# ATmega328P.net
KiCad netlist of a schematic drawn in Altium Designer
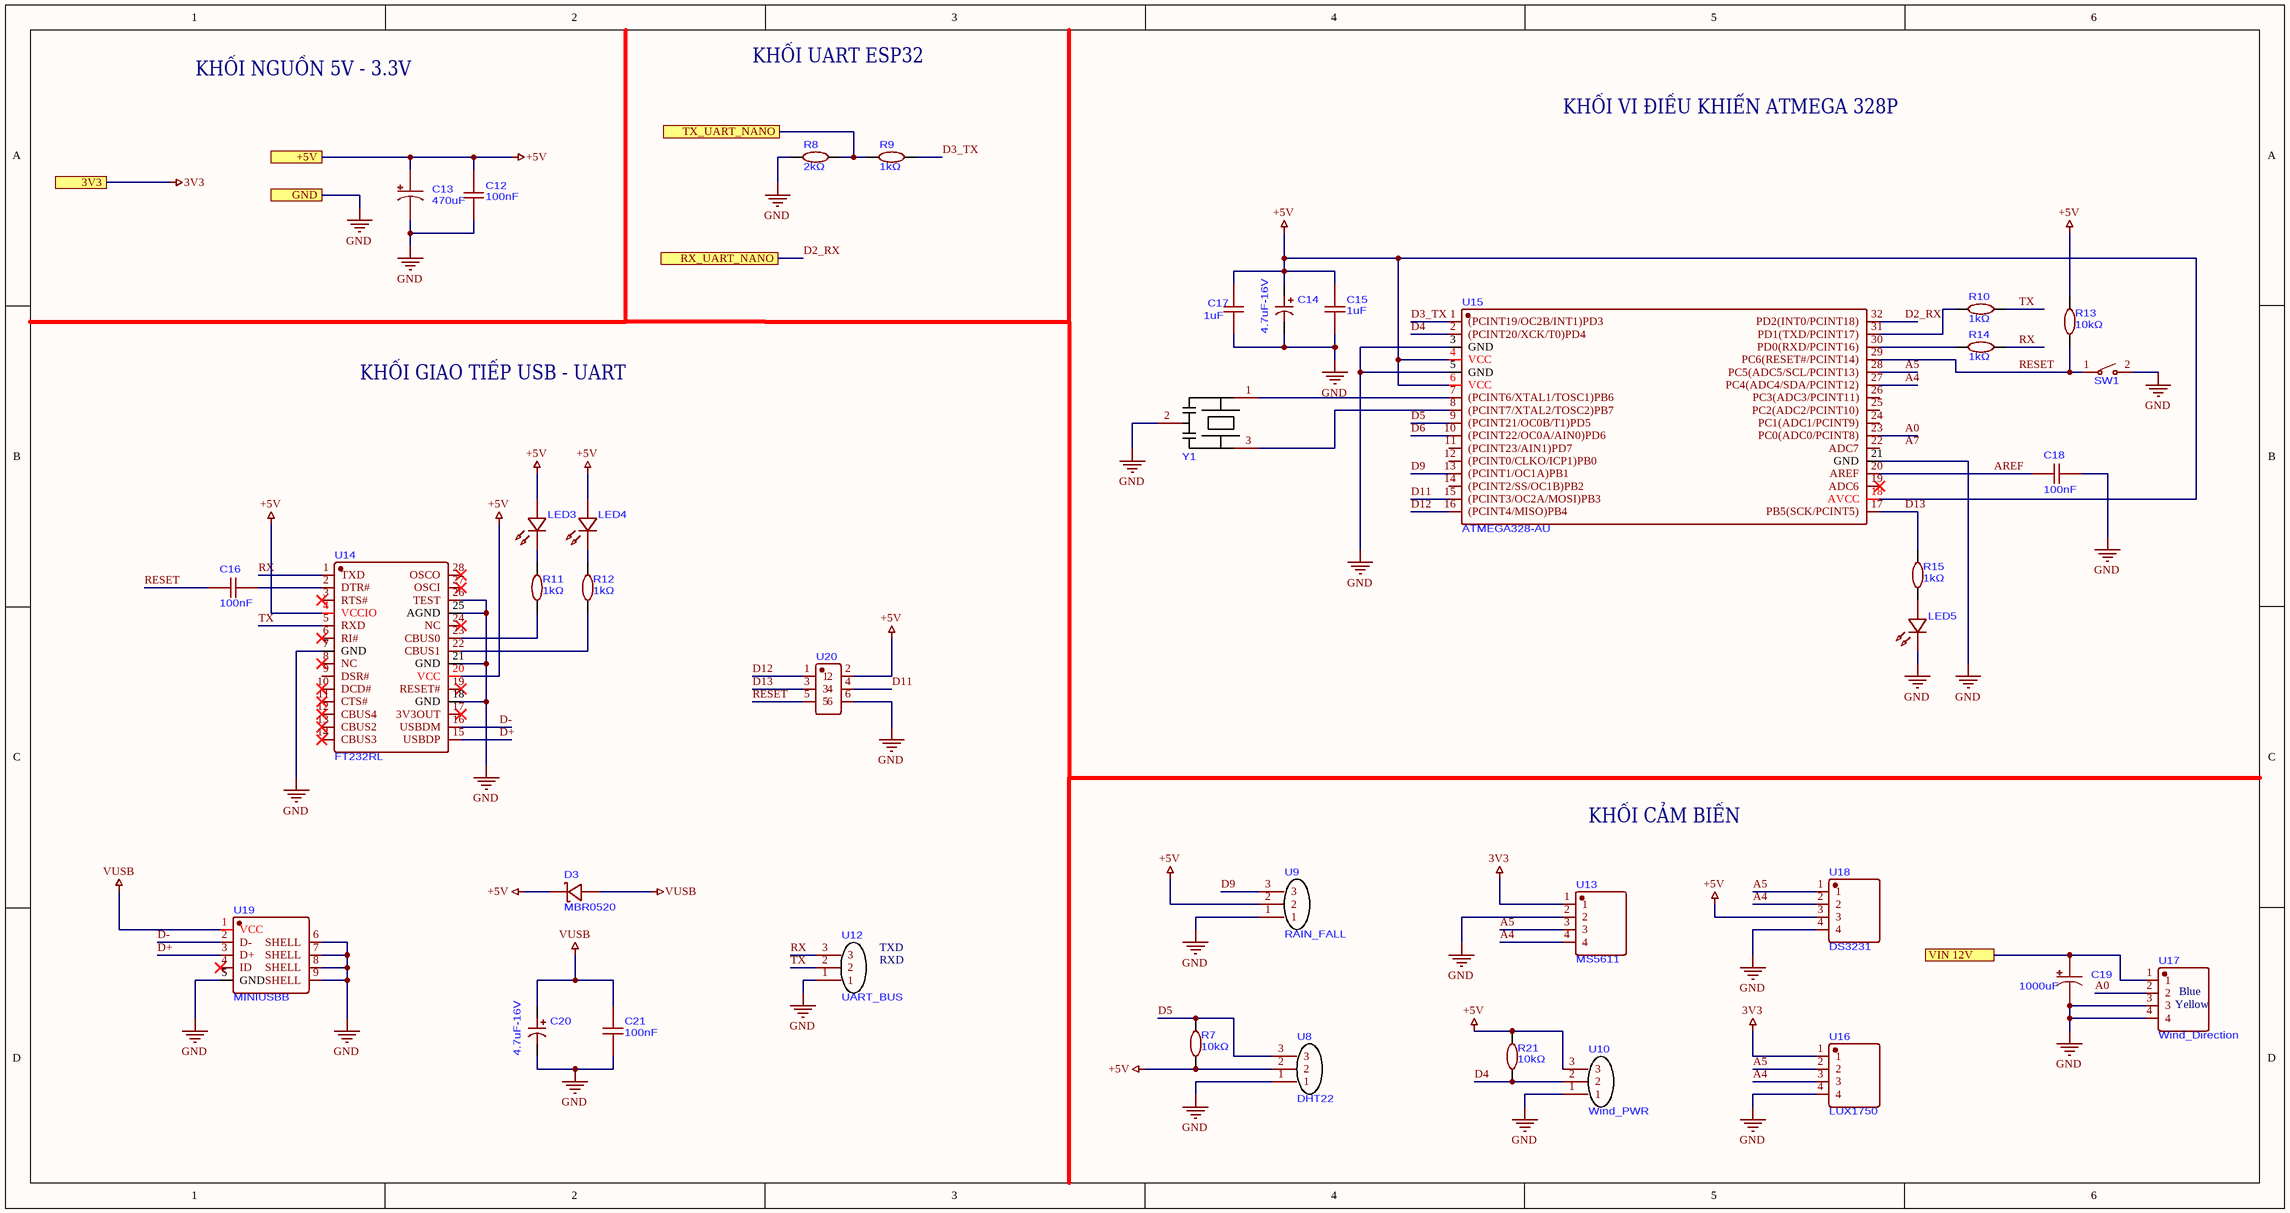
[diagram p0: ATmega328P.SchDoc]

(export (version "E")
  (design (tool "Eeschema 10.0.6"))
  (components
    (comp (ref "C12")
      (value "100nF")
      (footprint "C0805")
      (libsource (lib "CAP 0.1uF") (part "CC0805KRX7R9BB104"))
    )
    (comp (ref "C13")
      (value "470uF")
      (footprint "CAP-SMD_BD10.0-L10.3-W10.3-LS11.0-R-RD")
      (libsource (lib "CAP +") (part "VEJ102M1ATR-1010"))
    )
    (comp (ref "C14")
      (value "4.7uF-16V")
      (footprint "CAP-SMD_L6.0-W3.2-FD")
      (libsource (lib "CAP + 4.7 uF") (part "TCJC475M063R0200"))
    )
    (comp (ref "C15")
      (value "1uF")
      (footprint "C0805")
      (libsource (lib "cap 1uF_0805") (part "TCC0805X7R105K250DTS"))
    )
    (comp (ref "C16")
      (value "100nF")
      (footprint "C0805")
      (libsource (lib "CAP 0.1uF") (part "CC0805KRX7R9BB104"))
    )
    (comp (ref "C17")
      (value "1uF")
      (footprint "C0805")
      (libsource (lib "cap 1uF_0805") (part "TCC0805X7R105K250DTS"))
    )
    (comp (ref "C18")
      (value "100nF")
      (footprint "C0805")
      (libsource (lib "CAP 0.1uF") (part "CC0805KRX7R9BB104"))
    )
    (comp (ref "C19")
      (value "1000uF")
      (footprint "CAP-SMD_BD10.0-L10.3-W10.3-LS11.0-R-RD")
      (libsource (lib "CAP +") (part "VEJ102M1ATR-1010"))
    )
    (comp (ref "C20")
      (value "4.7uF-16V")
      (footprint "CAP-SMD_L6.0-W3.2-FD")
      (libsource (lib "CAP + 4.7 uF") (part "TCJC475M063R0200"))
    )
    (comp (ref "C21")
      (value "100nF")
      (footprint "C0805")
      (libsource (lib "CAP 0.1uF") (part "CC0805KRX7R9BB104"))
    )
    (comp (ref "D3")
      (value "MBR0520")
      (footprint "SOD-123_L2.8-W1.8-LS3.7-RD")
      (libsource (lib "MBR0520") (part "MBR0520"))
    )
    (comp (ref "LED3")
      (value "XL-2012SURC")
      (footprint "LED0805-RD_RED")
      (libsource (lib "LED_RED") (part "XL-2012SURC"))
    )
    (comp (ref "LED4")
      (value "XL-2012SURC")
      (footprint "LED0805-RD_RED")
      (libsource (lib "LED_RED") (part "XL-2012SURC"))
    )
    (comp (ref "LED5")
      (value "XL-2012SURC")
      (footprint "LED0805-RD_RED")
      (libsource (lib "LED_RED") (part "XL-2012SURC"))
    )
    (comp (ref "R7") (value "10kΩ") (footprint "R0805") (libsource (lib "RES 1K") (part "RC0805FR-071KL")))
    (comp (ref "R8") (value "2kΩ") (footprint "R0805") (libsource (lib "RES 1K") (part "RC0805FR-071KL")))
    (comp (ref "R9") (value "1kΩ") (footprint "R0805") (libsource (lib "RES 1K") (part "RC0805FR-071KL")))
    (comp (ref "R10") (value "1kΩ") (footprint "R0805") (libsource (lib "RES 1K") (part "RC0805FR-071KL")))
    (comp (ref "R11") (value "1kΩ") (footprint "R0805") (libsource (lib "RES 1K") (part "RC0805FR-071KL")))
    (comp (ref "R12") (value "1kΩ") (footprint "R0805") (libsource (lib "RES 1K") (part "RC0805FR-071KL")))
    (comp (ref "R13") (value "10kΩ") (footprint "R0805") (libsource (lib "RES 1K") (part "RC0805FR-071KL")))
    (comp (ref "R14") (value "1kΩ") (footprint "R0805") (libsource (lib "RES 1K") (part "RC0805FR-071KL")))
    (comp (ref "R15") (value "1kΩ") (footprint "R0805") (libsource (lib "RES 1K") (part "RC0805FR-071KL")))
    (comp (ref "R21") (value "10kΩ") (footprint "R0805") (libsource (lib "RES 1K") (part "RC0805FR-071KL")))
    (comp (ref "SW1")
      (value "TS-1088R-02026")
      (footprint "SW-SMD_L3.9-W3.0-P4.45")
      (libsource (lib "switch_2P") (part "TS-1088R-02026"))
    )
    (comp (ref "U8")
      (value "DHT22")
      (footprint "CONN-TH_3P-P2.50_A2501WV2-3P")
      (libsource (lib "header 3x2") (part "B3B-XH-A(LF)(SN)"))
    )
    (comp (ref "U9")
      (value "RAIN_FALL")
      (footprint "CONN-TH_3P-P2.50_A2501WV2-3P")
      (libsource (lib "header 3x2") (part "B3B-XH-A(LF)(SN)"))
    )
    (comp (ref "U10")
      (value "Wind_PWR")
      (footprint "CONN-TH_3P-P2.50_A2501WV2-3P")
      (libsource (lib "header 3x2") (part "B3B-XH-A(LF)(SN)"))
    )
    (comp (ref "U12")
      (value "UART_BUS")
      (footprint "CONN-TH_3P-P2.50_A2501WV2-3P")
      (libsource (lib "header 3x2") (part "B3B-XH-A(LF)(SN)"))
    )
    (comp (ref "U13")
      (value "MS5611")
      (footprint "CONN-TH_B4B-XH-A-LF-SN")
      (libsource (lib "header 1p") (part "B4B-XH-A(LF)(SN)"))
    )
    (comp (ref "U14")
      (value "FT232RL")
      (footprint "SSOP-28_L10.2-W5.3-P0.65-LS7.8-BL")
      (libsource (lib "FT232Rl") (part "FT232RL"))
    )
    (comp (ref "U15")
      (value "ATMEGA328-AU")
      (footprint "TQFP-32_L7.0-W7.0-P0.80-LS9.0-BL")
      (libsource (lib "ATMEGA328_AU") (part "ATMEGA328-AU"))
    )
    (comp (ref "U16")
      (value "LUX1750")
      (footprint "CONN-TH_B4B-XH-A-LF-SN")
      (libsource (lib "header 1p") (part "B4B-XH-A(LF)(SN)"))
    )
    (comp (ref "U17")
      (value "Wind_Direction")
      (footprint "CONN-TH_B4B-XH-A-LF-SN")
      (libsource (lib "header 1p") (part "B4B-XH-A(LF)(SN)"))
    )
    (comp (ref "U18")
      (value "DS3231")
      (footprint "CONN-TH_B4B-XH-A-LF-SN")
      (libsource (lib "header 1p") (part "B4B-XH-A(LF)(SN)"))
    )
    (comp (ref "U19")
      (value "MINIUSBB")
      (footprint "USB-SMD_MINIUSBB")
      (libsource (lib "USM_MINIIII") (part "MINIUSBB"))
    )
    (comp (ref "U20")
      (value "BX-PZ2.54-2-3PZZ")
      (footprint "HDR-TH_6P-P2.54-V-M-R2-C3-S2.54")
      (libsource (lib "header 3x2") (part "BX-PZ2.54-2-3PZZ"))
    )
    (comp (ref "Y1")
      (value "CSTNE16M0V530000R0")
      (footprint "CSTNE16M0V530000R0")
      (libsource (lib "cystal_16Mhz_15pF") (part "CSTNE16M0V530000R0"))
    )
  )
  (nets
    (net (code "1") (name "+5V") (class "Default")
      (node (ref "C12") (pin "2") (pinfunction "2_2") (pintype "passive"))
      (node (ref "C13") (pin "1") (pinfunction "1_1") (pintype "passive"))
      (node (ref "C14") (pin "1") (pinfunction "1_1") (pintype "passive"))
      (node (ref "C15") (pin "1") (pinfunction "1_1") (pintype "passive"))
      (node (ref "C17") (pin "1") (pinfunction "1_1") (pintype "passive"))
      (node (ref "D3") (pin "1") (pinfunction "K_1") (pintype "passive"))
      (node (ref "LED3") (pin "2") (pinfunction "A_2") (pintype "passive"))
      (node (ref "LED4") (pin "2") (pinfunction "A_2") (pintype "passive"))
      (node (ref "R13") (pin "2") (pinfunction "2_2") (pintype "passive"))
      (node (ref "R21") (pin "1") (pinfunction "1_1") (pintype "passive"))
      (node (ref "R7") (pin "2") (pinfunction "2_2") (pintype "passive"))
      (node (ref "U10") (pin "3") (pinfunction "3_3") (pintype "passive"))
      (node (ref "U14") (pin "20") (pinfunction "VCC_20") (pintype "passive"))
      (node (ref "U14") (pin "4") (pinfunction "VCCIO_4") (pintype "passive"))
      (node (ref "U15") (pin "18") (pinfunction "AVCC_18") (pintype "passive"))
      (node (ref "U15") (pin "4") (pinfunction "VCC_4") (pintype "passive"))
      (node (ref "U15") (pin "6") (pinfunction "VCC_6") (pintype "passive"))
      (node (ref "U18") (pin "3") (pinfunction "3_3") (pintype "passive"))
      (node (ref "U20") (pin "2") (pinfunction "2_2") (pintype "passive"))
      (node (ref "U8") (pin "2") (pinfunction "2_2") (pintype "passive"))
      (node (ref "U9") (pin "2") (pinfunction "2_2") (pintype "passive"))
    )
    (net (code "2") (name "/A0") (class "Default")
      (node (ref "U15") (pin "23") (pinfunction "PC0(ADC0/PCINT8)_23") (pintype "passive"))
      (node (ref "U17") (pin "2") (pinfunction "2_2") (pintype "passive"))
    )
    (net (code "3") (name "/A4") (class "Default")
      (node (ref "U13") (pin "4") (pinfunction "4_4") (pintype "passive"))
      (node (ref "U15") (pin "27") (pinfunction "PC4(ADC4/SDA/PCINT12)_27") (pintype "passive"))
      (node (ref "U16") (pin "3") (pinfunction "3_3") (pintype "passive"))
      (node (ref "U18") (pin "2") (pinfunction "2_2") (pintype "passive"))
    )
    (net (code "4") (name "/A5") (class "Default")
      (node (ref "U13") (pin "3") (pinfunction "3_3") (pintype "passive"))
      (node (ref "U15") (pin "28") (pinfunction "PC5(ADC5/SCL/PCINT13)_28") (pintype "passive"))
      (node (ref "U16") (pin "2") (pinfunction "2_2") (pintype "passive"))
      (node (ref "U18") (pin "1") (pinfunction "1_1") (pintype "passive"))
    )
    (net (code "6") (name "/AREF") (class "Default")
      (node (ref "C18") (pin "1") (pinfunction "1_1") (pintype "passive"))
      (node (ref "U15") (pin "20") (pinfunction "AREF_20") (pintype "passive"))
    )
    (net (code "7") (name "/D+") (class "Default")
      (node (ref "U14") (pin "15") (pinfunction "USBDP_15") (pintype "passive"))
      (node (ref "U19") (pin "3") (pinfunction "D+_3") (pintype "passive"))
    )
    (net (code "8") (name "/D-") (class "Default")
      (node (ref "U14") (pin "16") (pinfunction "USBDM_16") (pintype "passive"))
      (node (ref "U19") (pin "2") (pinfunction "D-_2") (pintype "passive"))
    )
    (net (code "9") (name "/D2_RX") (class "Default")
      (node (ref "U15") (pin "32") (pinfunction "PD2(INT0/PCINT18)_32") (pintype "passive"))
    )
    (net (code "10") (name "/D3_TX") (class "Default")
      (node (ref "R9") (pin "2") (pinfunction "2_2") (pintype "passive"))
      (node (ref "U15") (pin "1") (pinfunction "(PCINT19/OC2B/INT1)PD3_1") (pintype "passive"))
    )
    (net (code "11") (name "/D4") (class "Default")
      (node (ref "R21") (pin "2") (pinfunction "2_2") (pintype "passive"))
      (node (ref "U10") (pin "2") (pinfunction "2_2") (pintype "passive"))
      (node (ref "U15") (pin "2") (pinfunction "(PCINT20/XCK/T0)PD4_2") (pintype "passive"))
    )
    (net (code "12") (name "/D5") (class "Default")
      (node (ref "R7") (pin "1") (pinfunction "1_1") (pintype "passive"))
      (node (ref "U15") (pin "9") (pinfunction "(PCINT21/OC0B/T1)PD5_9") (pintype "passive"))
      (node (ref "U8") (pin "3") (pinfunction "3_3") (pintype "passive"))
    )
    (net (code "13") (name "/D6") (class "Default")
      (node (ref "U15") (pin "10") (pinfunction "(PCINT22/OC0A/AIN0)PD6_10") (pintype "passive"))
    )
    (net (code "14") (name "/D9") (class "Default")
      (node (ref "U15") (pin "13") (pinfunction "(PCINT1/OC1A)PB1_13") (pintype "passive"))
      (node (ref "U9") (pin "3") (pinfunction "3_3") (pintype "passive"))
    )
    (net (code "15") (name "/D11") (class "Default")
      (node (ref "U15") (pin "15") (pinfunction "(PCINT3/OC2A/MOSI)PB3_15") (pintype "passive"))
      (node (ref "U20") (pin "4") (pinfunction "4_4") (pintype "passive"))
    )
    (net (code "16") (name "/D12") (class "Default")
      (node (ref "U15") (pin "16") (pinfunction "(PCINT4/MISO)PB4_16") (pintype "passive"))
      (node (ref "U20") (pin "1") (pinfunction "1_1") (pintype "passive"))
    )
    (net (code "17") (name "/D13") (class "Default")
      (node (ref "R15") (pin "2") (pinfunction "2_2") (pintype "passive"))
      (node (ref "U15") (pin "17") (pinfunction "PB5(SCK/PCINT5)_17") (pintype "passive"))
      (node (ref "U20") (pin "3") (pinfunction "3_3") (pintype "passive"))
    )
    (net (code "18") (name "/RESET") (class "Default")
      (node (ref "C16") (pin "1") (pinfunction "1_1") (pintype "passive"))
      (node (ref "R13") (pin "1") (pinfunction "1_1") (pintype "passive"))
      (node (ref "SW1") (pin "1") (pinfunction "1_1") (pintype "passive"))
      (node (ref "U15") (pin "29") (pinfunction "PC6(RESET#/PCINT14)_29") (pintype "passive"))
      (node (ref "U20") (pin "5") (pinfunction "5_5") (pintype "passive"))
    )
    (net (code "19") (name "/RX") (class "Default")
      (node (ref "R14") (pin "1") (pinfunction "1_1") (pintype "passive"))
      (node (ref "U12") (pin "3") (pinfunction "3_3") (pintype "passive"))
      (node (ref "U14") (pin "1") (pinfunction "TXD_1") (pintype "passive"))
    )
    (net (code "20") (name "/TX") (class "Default")
      (node (ref "R10") (pin "1") (pinfunction "1_1") (pintype "passive"))
      (node (ref "U12") (pin "2") (pinfunction "2_2") (pintype "passive"))
      (node (ref "U14") (pin "5") (pinfunction "RXD_5") (pintype "passive"))
    )
    (net (code "21") (name "/TX_UART_NANO") (class "Default")
      (node (ref "R8") (pin "2") (pinfunction "2_2") (pintype "passive"))
      (node (ref "R9") (pin "1") (pinfunction "1_1") (pintype "passive"))
    )
    (net (code "22") (name "/VIN 12V") (class "Default")
      (node (ref "C19") (pin "1") (pinfunction "1_1") (pintype "passive"))
      (node (ref "U17") (pin "1") (pinfunction "1_1") (pintype "passive"))
    )
    (net (code "23") (name "3V3") (class "Default")
      (node (ref "U13") (pin "1") (pinfunction "1_1") (pintype "passive"))
      (node (ref "U16") (pin "1") (pinfunction "1_1") (pintype "passive"))
    )
    (net (code "24") (name "GND") (class "Default")
      (node (ref "C12") (pin "1") (pinfunction "1_1") (pintype "passive"))
      (node (ref "C13") (pin "2") (pinfunction "2_2") (pintype "passive"))
      (node (ref "C14") (pin "2") (pinfunction "2_2") (pintype "passive"))
      (node (ref "C15") (pin "2") (pinfunction "2_2") (pintype "passive"))
      (node (ref "C17") (pin "2") (pinfunction "2_2") (pintype "passive"))
      (node (ref "C18") (pin "2") (pinfunction "2_2") (pintype "passive"))
      (node (ref "C19") (pin "2") (pinfunction "2_2") (pintype "passive"))
      (node (ref "C20") (pin "2") (pinfunction "2_2") (pintype "passive"))
      (node (ref "C21") (pin "1") (pinfunction "1_1") (pintype "passive"))
      (node (ref "LED5") (pin "1") (pinfunction "K_1") (pintype "passive"))
      (node (ref "R8") (pin "1") (pinfunction "1_1") (pintype "passive"))
      (node (ref "SW1") (pin "2") (pinfunction "2_2") (pintype "passive"))
      (node (ref "U10") (pin "1") (pinfunction "1_1") (pintype "passive"))
      (node (ref "U12") (pin "1") (pinfunction "1_1") (pintype "passive"))
      (node (ref "U13") (pin "2") (pinfunction "2_2") (pintype "passive"))
      (node (ref "U14") (pin "18") (pinfunction "GND_18") (pintype "passive"))
      (node (ref "U14") (pin "21") (pinfunction "GND_21") (pintype "passive"))
      (node (ref "U14") (pin "25") (pinfunction "AGND_25") (pintype "passive"))
      (node (ref "U14") (pin "26") (pinfunction "TEST_26") (pintype "passive"))
      (node (ref "U14") (pin "7") (pinfunction "GND_7") (pintype "passive"))
      (node (ref "U15") (pin "21") (pinfunction "GND_21") (pintype "passive"))
      (node (ref "U15") (pin "3") (pinfunction "GND_3") (pintype "passive"))
      (node (ref "U15") (pin "5") (pinfunction "GND_5") (pintype "passive"))
      (node (ref "U16") (pin "4") (pinfunction "4_4") (pintype "passive"))
      (node (ref "U17") (pin "3") (pinfunction "3_3") (pintype "passive"))
      (node (ref "U17") (pin "4") (pinfunction "4_4") (pintype "passive"))
      (node (ref "U18") (pin "4") (pinfunction "4_4") (pintype "passive"))
      (node (ref "U19") (pin "5") (pinfunction "GND_5") (pintype "passive"))
      (node (ref "U19") (pin "6") (pinfunction "SHELL_6") (pintype "passive"))
      (node (ref "U19") (pin "7") (pinfunction "SHELL_7") (pintype "passive"))
      (node (ref "U19") (pin "8") (pinfunction "SHELL_8") (pintype "passive"))
      (node (ref "U19") (pin "9") (pinfunction "SHELL_9") (pintype "passive"))
      (node (ref "U20") (pin "6") (pinfunction "6_6") (pintype "passive"))
      (node (ref "U8") (pin "1") (pinfunction "1_1") (pintype "passive"))
      (node (ref "U9") (pin "1") (pinfunction "1_1") (pintype "passive"))
      (node (ref "Y1") (pin "2") (pinfunction "2_2") (pintype "passive"))
    )
    (net (code "25") (name "Net-(LED3-K)") (class "Default")
      (node (ref "LED3") (pin "1") (pinfunction "K_1") (pintype "passive"))
      (node (ref "R11") (pin "2") (pinfunction "2_2") (pintype "passive"))
    )
    (net (code "26") (name "Net-(LED4-K)") (class "Default")
      (node (ref "LED4") (pin "1") (pinfunction "K_1") (pintype "passive"))
      (node (ref "R12") (pin "2") (pinfunction "2_2") (pintype "passive"))
    )
    (net (code "27") (name "Net-(LED5-A)") (class "Default")
      (node (ref "LED5") (pin "2") (pinfunction "A_2") (pintype "passive"))
      (node (ref "R15") (pin "1") (pinfunction "1_1") (pintype "passive"))
    )
    (net (code "28") (name "Net-(U14-CBUS0)") (class "Default")
      (node (ref "R11") (pin "1") (pinfunction "1_1") (pintype "passive"))
      (node (ref "U14") (pin "23") (pinfunction "CBUS0_23") (pintype "passive"))
    )
    (net (code "29") (name "Net-(U14-CBUS1)") (class "Default")
      (node (ref "R12") (pin "1") (pinfunction "1_1") (pintype "passive"))
      (node (ref "U14") (pin "22") (pinfunction "CBUS1_22") (pintype "passive"))
    )
    (net (code "30") (name "Net-(U14-DTR#)") (class "Default")
      (node (ref "C16") (pin "2") (pinfunction "2_2") (pintype "passive"))
      (node (ref "U14") (pin "2") (pinfunction "DTR#_2") (pintype "passive"))
    )
    (net (code "31") (name "Net-(U15-(PCINT6{slash}XTAL1{slash}TOSC1)PB6)") (class "Default")
      (node (ref "U15") (pin "7") (pinfunction "(PCINT6/XTAL1/TOSC1)PB6_7") (pintype "passive"))
      (node (ref "Y1") (pin "1") (pinfunction "1_1") (pintype "passive"))
    )
    (net (code "32") (name "Net-(U15-(PCINT7{slash}XTAL2{slash}TOSC2)PB7)") (class "Default")
      (node (ref "U15") (pin "8") (pinfunction "(PCINT7/XTAL2/TOSC2)PB7_8") (pintype "passive"))
      (node (ref "Y1") (pin "3") (pinfunction "3_3") (pintype "passive"))
    )
    (net (code "33") (name "Net-(U15-PD0(RXD{slash}PCINT16))") (class "Default")
      (node (ref "R14") (pin "2") (pinfunction "2_2") (pintype "passive"))
      (node (ref "U15") (pin "30") (pinfunction "PD0(RXD/PCINT16)_30") (pintype "passive"))
    )
    (net (code "34") (name "Net-(U15-PD1(TXD{slash}PCINT17))") (class "Default")
      (node (ref "R10") (pin "2") (pinfunction "2_2") (pintype "passive"))
      (node (ref "U15") (pin "31") (pinfunction "PD1(TXD/PCINT17)_31") (pintype "passive"))
    )
    (net (code "35") (name "VUSB") (class "Default")
      (node (ref "C20") (pin "1") (pinfunction "1_1") (pintype "passive"))
      (node (ref "C21") (pin "2") (pinfunction "2_2") (pintype "passive"))
      (node (ref "D3") (pin "2") (pinfunction "A_2") (pintype "passive"))
      (node (ref "U19") (pin "1") (pinfunction "VCC_1") (pintype "passive"))
    )
    (net (code "36") (name "unconnected-(U14-3V3OUT-Pad17)") (class "Default")
      (node (ref "U14") (pin "17") (pinfunction "3V3OUT_17") (pintype "passive+no_connect"))
    )
    (net (code "37") (name "unconnected-(U14-CBUS2-Pad13)") (class "Default")
      (node (ref "U14") (pin "13") (pinfunction "CBUS2_13") (pintype "passive+no_connect"))
    )
    (net (code "38") (name "unconnected-(U14-CBUS3-Pad14)") (class "Default")
      (node (ref "U14") (pin "14") (pinfunction "CBUS3_14") (pintype "passive+no_connect"))
    )
    (net (code "39") (name "unconnected-(U14-CBUS4-Pad12)") (class "Default")
      (node (ref "U14") (pin "12") (pinfunction "CBUS4_12") (pintype "passive+no_connect"))
    )
    (net (code "40") (name "unconnected-(U14-CTS#-Pad11)") (class "Default")
      (node (ref "U14") (pin "11") (pinfunction "CTS#_11") (pintype "passive+no_connect"))
    )
    (net (code "41") (name "unconnected-(U14-DCD#-Pad10)") (class "Default")
      (node (ref "U14") (pin "10") (pinfunction "DCD#_10") (pintype "passive+no_connect"))
    )
    (net (code "42") (name "unconnected-(U14-DSR#-Pad9)") (class "Default")
      (node (ref "U14") (pin "9") (pinfunction "DSR#_9") (pintype "passive"))
    )
    (net (code "43") (name "unconnected-(U14-NC-Pad8)") (class "Default")
      (node (ref "U14") (pin "8") (pinfunction "NC_8") (pintype "passive+no_connect"))
    )
    (net (code "44") (name "unconnected-(U14-NC-Pad24)") (class "Default")
      (node (ref "U14") (pin "24") (pinfunction "NC_24") (pintype "passive+no_connect"))
    )
    (net (code "45") (name "unconnected-(U14-OSCI-Pad27)") (class "Default")
      (node (ref "U14") (pin "27") (pinfunction "OSCI_27") (pintype "passive+no_connect"))
    )
    (net (code "46") (name "unconnected-(U14-OSCO-Pad28)") (class "Default")
      (node (ref "U14") (pin "28") (pinfunction "OSCO_28") (pintype "passive+no_connect"))
    )
    (net (code "47") (name "unconnected-(U14-RESET#-Pad19)") (class "Default")
      (node (ref "U14") (pin "19") (pinfunction "RESET#_19") (pintype "passive+no_connect"))
    )
    (net (code "48") (name "unconnected-(U14-RI#-Pad6)") (class "Default")
      (node (ref "U14") (pin "6") (pinfunction "RI#_6") (pintype "passive+no_connect"))
    )
    (net (code "49") (name "unconnected-(U14-RTS#-Pad3)") (class "Default")
      (node (ref "U14") (pin "3") (pinfunction "RTS#_3") (pintype "passive+no_connect"))
    )
    (net (code "50") (name "unconnected-(U15-(PCINT0{slash}CLKO{slash}ICP1)PB0-Pad12)") (class "Default")
      (node (ref "U15") (pin "12") (pinfunction "(PCINT0/CLKO/ICP1)PB0_12") (pintype "passive"))
    )
    (net (code "51") (name "unconnected-(U15-(PCINT2{slash}SS{slash}OC1B)PB2-Pad14)") (class "Default")
      (node (ref "U15") (pin "14") (pinfunction "(PCINT2/SS/OC1B)PB2_14") (pintype "passive"))
    )
    (net (code "52") (name "unconnected-(U15-(PCINT23{slash}AIN1)PD7-Pad11)") (class "Default")
      (node (ref "U15") (pin "11") (pinfunction "(PCINT23/AIN1)PD7_11") (pintype "passive"))
    )
    (net (code "53") (name "unconnected-(U15-ADC6-Pad19)") (class "Default")
      (node (ref "U15") (pin "19") (pinfunction "ADC6_19") (pintype "passive+no_connect"))
    )
    (net (code "54") (name "unconnected-(U15-ADC7-Pad22)") (class "Default")
      (node (ref "U15") (pin "22") (pinfunction "ADC7_22") (pintype "passive"))
    )
    (net (code "55") (name "unconnected-(U15-PC1(ADC1{slash}PCINT9)-Pad24)") (class "Default")
      (node (ref "U15") (pin "24") (pinfunction "PC1(ADC1/PCINT9)_24") (pintype "passive"))
    )
    (net (code "56") (name "unconnected-(U15-PC2(ADC2{slash}PCINT10)-Pad25)") (class "Default")
      (node (ref "U15") (pin "25") (pinfunction "PC2(ADC2/PCINT10)_25") (pintype "passive"))
    )
    (net (code "57") (name "unconnected-(U15-PC3(ADC3{slash}PCINT11)-Pad26)") (class "Default")
      (node (ref "U15") (pin "26") (pinfunction "PC3(ADC3/PCINT11)_26") (pintype "passive"))
    )
    (net (code "58") (name "unconnected-(U19-ID-Pad4)") (class "Default")
      (node (ref "U19") (pin "4") (pinfunction "ID_4") (pintype "passive+no_connect"))
    )
  )
)
